# w43TrafficLight_schematic.net
KiCad netlist of a schematic drawn in Altium Designer
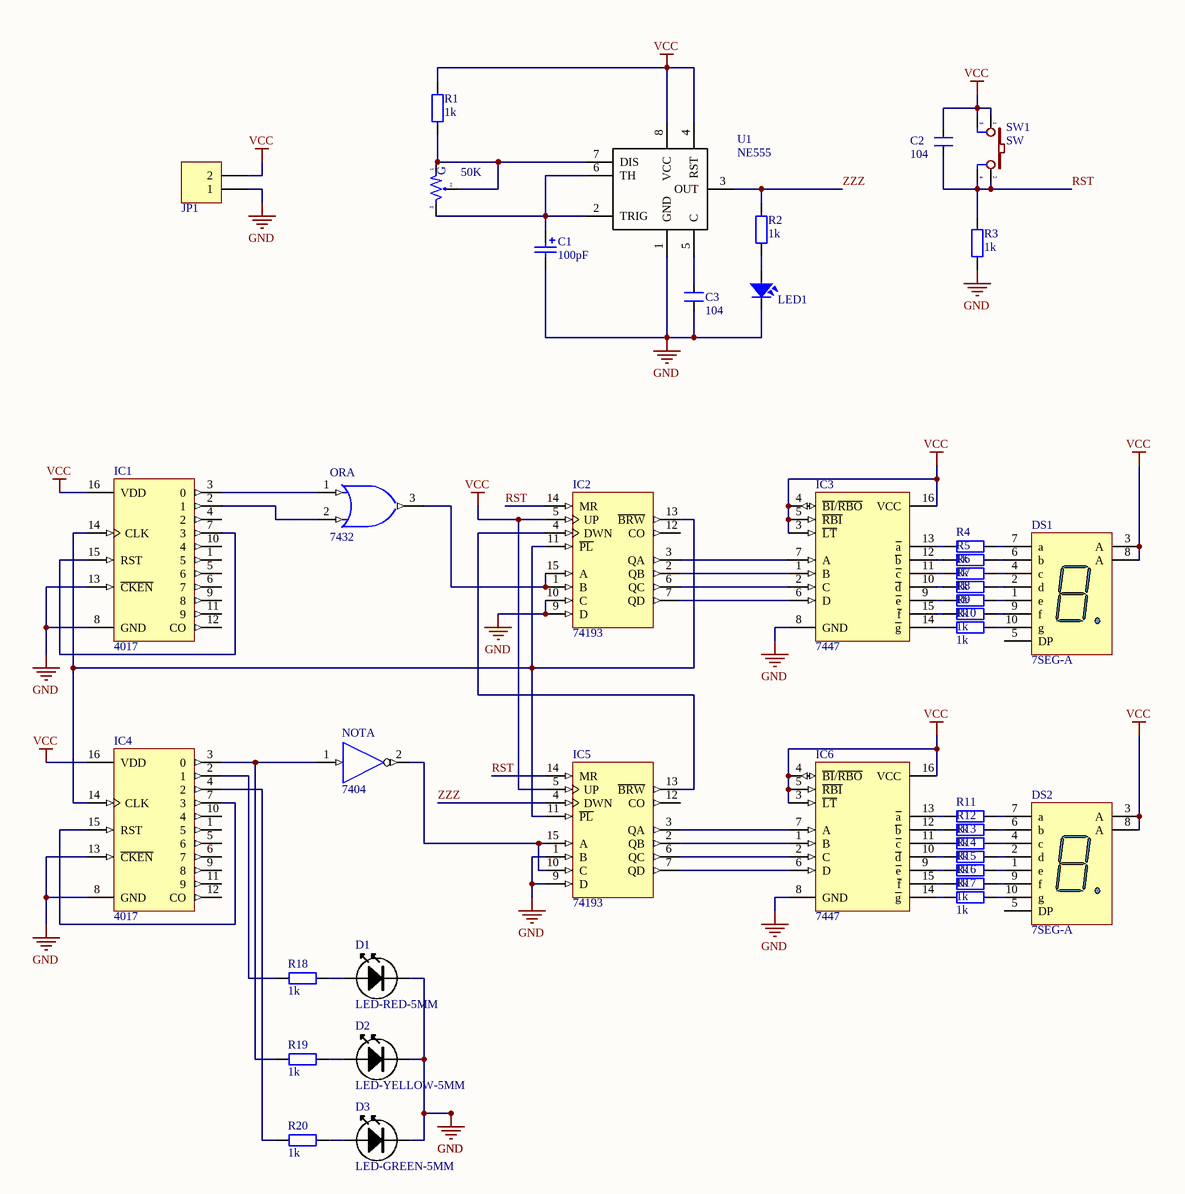
[diagram p0: w43TrafficLight_schematic.SchDoc]

(export (version "E")
  (design (tool "Eeschema 10.0.6"))
  (components
    (comp (ref "C1")
      (value "100pF")
      (footprint "CP1/2")
      (description "Polarized Capacitor (Radial)")
      (fields (field (name "Comment") "Cap Pol"))
      (libsource (lib "PIF_Library") (part "Cap Pol"))
    )
    (comp (ref "C2")
      (value "104")
      (footprint "CN150")
      (description "Capacitor Ceramic")
      (libsource (lib "SRC") (part "CN1.5"))
    )
    (comp (ref "C3")
      (value "104")
      (footprint "CN150")
      (description "Capacitor Ceramic")
      (libsource (lib "SRC") (part "CN1.5"))
    )
    (comp (ref "D1")
      (value "LED-RED-5MM")
      (footprint "LED-5MM-RED")
      (libsource (lib "vh_altium_library") (part "LED-RED-5MM"))
    )
    (comp (ref "D2")
      (value "LED-YELLOW-5MM")
      (footprint "LED-5MM-YELLOW")
      (libsource (lib "vh_altium_library") (part "LED-YELLOW-5MM"))
    )
    (comp (ref "D3")
      (value "LED-GREEN-5MM")
      (footprint "LED-5MM-GREEN")
      (libsource (lib "vh_altium_library") (part "LED-GREEN-5MM"))
    )
    (comp (ref "DS1")
      (value "7SEG-A")
      (footprint "LED7SEG")
      (description "14.2 mm General Purpose Blue 7-Segment Display: CA, RH DP, Gray Surface")
      (fields (field (name "PUBLISHER") "Altium Limited"))
      (libsource (lib "NBBLib-14-03-2012") (part "LED7SEG-A"))
    )
    (comp (ref "DS2")
      (value "7SEG-A")
      (footprint "LED7SEG")
      (description "14.2 mm General Purpose Blue 7-Segment Display: CA, RH DP, Gray Surface")
      (fields (field (name "PUBLISHER") "Altium Limited"))
      (libsource (lib "NBBLib-14-03-2012") (part "LED7SEG-A"))
    )
    (comp (ref "IC1")
      (value "4017")
      (footprint "DIP16")
      (description "Decade Counter/Divider with 10 Decoded Outputs")
      (fields (field (name "DESIGNED BY") "VanDungEvn"))
      (libsource (lib "LIBRARY") (part "4017"))
    )
    (comp (ref "IC2")
      (value "74193")
      (footprint "DIP16/W0.3")
      (description "Synchronous 4-Bit Up/Down Counter")
      (fields (field (name "COPYRIGHT BY") "VanDungEvn@Gmail.com"))
      (libsource (lib "takahashi") (part "74193"))
    )
    (comp (ref "IC3")
      (value "7447")
      (footprint "DIP16")
      (description "BCD to 7-Segment Decoder/Driver")
      (libsource (lib "LIBRARY") (part "7447"))
    )
    (comp (ref "IC4")
      (value "4017")
      (footprint "DIP16")
      (description "Decade Counter/Divider with 10 Decoded Outputs")
      (fields (field (name "DESIGNED BY") "VanDungEvn"))
      (libsource (lib "LIBRARY") (part "4017"))
    )
    (comp (ref "IC5")
      (value "74193")
      (footprint "DIP16/W0.3")
      (description "Synchronous 4-Bit Up/Down Counter")
      (fields (field (name "COPYRIGHT BY") "VanDungEvn@Gmail.com"))
      (libsource (lib "takahashi") (part "74193"))
    )
    (comp (ref "IC6")
      (value "7447")
      (footprint "DIP16")
      (description "BCD to 7-Segment Decoder/Driver")
      (libsource (lib "LIBRARY") (part "7447"))
    )
    (comp (ref "JP1")
      (value "Header 2_1")
      (footprint "HED2")
      (description "Header, 2-Pin")
      (fields (field (name "MANUFACTURER") "Generic Components"))
      (libsource (lib "takahashi") (part "Header 2_1"))
    )
    (comp (ref "LED1")
      (value "LED")
      (footprint "LED-3MM-WHITE")
      (description "LED Single colour Green and Red")
      (libsource (lib "LIBRARY") (part "LED"))
    )
    (comp (ref "NOT")
      (value "7404")
      (footprint "DIP14/W0.3")
      (description "Hex Inverter")
      (libsource (lib "takahashi") (part "7404"))
    )
    (comp (ref "OR")
      (value "7432")
      (footprint "DIP14/W0.3")
      (description "Quad 2-Input OR Gate")
      (libsource (lib "takahashi") (part "7432"))
    )
    (comp (ref "R1")
      (value "1k")
      (footprint "R1/4W")
      (description "Resistor 1/4W")
      (libsource (lib "syhaunguyen") (part "R1/4W"))
    )
    (comp (ref "R2")
      (value "1k")
      (footprint "R1/4W")
      (description "Resistor 1/4W")
      (libsource (lib "syhaunguyen") (part "R1/4W"))
    )
    (comp (ref "R3")
      (value "1k")
      (footprint "R1/4W")
      (description "Resistor 1/4W")
      (libsource (lib "syhaunguyen") (part "R1/4W"))
    )
    (comp (ref "R4")
      (value "1k")
      (footprint "R1/4W")
      (description "Resistor 1/4W")
      (libsource (lib "syhaunguyen") (part "R1/4W"))
    )
    (comp (ref "R5")
      (value "1k")
      (footprint "R1/4W")
      (description "Resistor 1/4W")
      (libsource (lib "syhaunguyen") (part "R1/4W"))
    )
    (comp (ref "R6")
      (value "1k")
      (footprint "R1/4W")
      (description "Resistor 1/4W")
      (libsource (lib "syhaunguyen") (part "R1/4W"))
    )
    (comp (ref "R7")
      (value "1k")
      (footprint "R1/4W")
      (description "Resistor 1/4W")
      (libsource (lib "syhaunguyen") (part "R1/4W"))
    )
    (comp (ref "R8")
      (value "1k")
      (footprint "R1/4W")
      (description "Resistor 1/4W")
      (libsource (lib "syhaunguyen") (part "R1/4W"))
    )
    (comp (ref "R9")
      (value "1k")
      (footprint "R1/4W")
      (description "Resistor 1/4W")
      (libsource (lib "syhaunguyen") (part "R1/4W"))
    )
    (comp (ref "R10")
      (value "1k")
      (footprint "R1/4W")
      (description "Resistor 1/4W")
      (libsource (lib "syhaunguyen") (part "R1/4W"))
    )
    (comp (ref "R11")
      (value "1k")
      (footprint "R1/4W")
      (description "Resistor 1/4W")
      (libsource (lib "syhaunguyen") (part "R1/4W"))
    )
    (comp (ref "R12")
      (value "1k")
      (footprint "R1/4W")
      (description "Resistor 1/4W")
      (libsource (lib "syhaunguyen") (part "R1/4W"))
    )
    (comp (ref "R13")
      (value "1k")
      (footprint "R1/4W")
      (description "Resistor 1/4W")
      (libsource (lib "syhaunguyen") (part "R1/4W"))
    )
    (comp (ref "R14")
      (value "1k")
      (footprint "R1/4W")
      (description "Resistor 1/4W")
      (libsource (lib "syhaunguyen") (part "R1/4W"))
    )
    (comp (ref "R15")
      (value "1k")
      (footprint "R1/4W")
      (description "Resistor 1/4W")
      (libsource (lib "syhaunguyen") (part "R1/4W"))
    )
    (comp (ref "R16")
      (value "1k")
      (footprint "R1/4W")
      (description "Resistor 1/4W")
      (libsource (lib "syhaunguyen") (part "R1/4W"))
    )
    (comp (ref "R17")
      (value "1k")
      (footprint "R1/4W")
      (description "Resistor 1/4W")
      (libsource (lib "syhaunguyen") (part "R1/4W"))
    )
    (comp (ref "R18")
      (value "1k")
      (footprint "R1/4W")
      (description "Resistor 1/4W")
      (libsource (lib "syhaunguyen") (part "R1/4W"))
    )
    (comp (ref "R19")
      (value "1k")
      (footprint "R1/4W")
      (description "Resistor 1/4W")
      (libsource (lib "syhaunguyen") (part "R1/4W"))
    )
    (comp (ref "R20")
      (value "1k")
      (footprint "R1/4W")
      (description "Resistor 1/4W")
      (libsource (lib "syhaunguyen") (part "R1/4W"))
    )
    (comp (ref "SW1")
      (value "SW")
      (footprint "SW4")
      (description "Switch button 4 pin")
      (libsource (lib "takahashi") (part "SW4-1"))
    )
    (comp (ref "U1")
      (value "NE555")
      (footprint "DIP8")
      (description "TIMER IC")
      (fields
        (field (name "MANUFACTURER PART NUMBER") "NE555DT")
        (field (name "MANUFACTURER") "STMicroelectronics")
      )
      (libsource (lib "LIBRARY") (part "NE555"))
    )
    (comp (ref "VR1")
      (value "50K")
      (footprint "VR-S1")
      (description "Var Resistor")
      (libsource (lib "LIBRARY") (part "VR-S"))
    )
  )
  (nets
    (net (code "1") (name "/RST") (class "Default")
      (node (ref "C2") (pin "1") (pinfunction "1_1") (pintype "passive"))
      (node (ref "IC2") (pin "14") (pinfunction "MR_14") (pintype "input"))
      (node (ref "IC5") (pin "14") (pinfunction "MR_14") (pintype "input"))
      (node (ref "R3") (pin "2") (pinfunction "2_2") (pintype "passive"))
      (node (ref "SW1") (pin "2") (pinfunction "2_2") (pintype "passive"))
      (node (ref "SW1") (pin "4") (pinfunction "4_4") (pintype "passive"))
    )
    (net (code "2") (name "/ZZZ") (class "Default")
      (node (ref "IC5") (pin "4") (pinfunction "DWN_4") (pintype "input"))
      (node (ref "R2") (pin "2") (pinfunction "2_2") (pintype "passive"))
      (node (ref "U1") (pin "3") (pinfunction "OUT_3") (pintype "passive"))
    )
    (net (code "3") (name "GND") (class "Default")
      (node (ref "C1") (pin "2") (pinfunction "2_2") (pintype "passive"))
      (node (ref "C3") (pin "1") (pinfunction "1_1") (pintype "passive"))
      (node (ref "D1") (pin "K") (pintype "passive"))
      (node (ref "D2") (pin "K") (pintype "passive"))
      (node (ref "D3") (pin "K") (pintype "passive"))
      (node (ref "IC1") (pin "13") (pinfunction "~{CKEN}_13") (pintype "input"))
      (node (ref "IC1") (pin "8") (pinfunction "GND_8") (pintype "power_in"))
      (node (ref "IC2") (pin "10") (pinfunction "C_10") (pintype "input"))
      (node (ref "IC2") (pin "8") (pinfunction "GND_8") (pintype "power_in"))
      (node (ref "IC2") (pin "9") (pinfunction "D_9") (pintype "input"))
      (node (ref "IC3") (pin "8") (pinfunction "GND_8") (pintype "power_in"))
      (node (ref "IC4") (pin "13") (pinfunction "~{CKEN}_13") (pintype "input"))
      (node (ref "IC4") (pin "8") (pinfunction "GND_8") (pintype "power_in"))
      (node (ref "IC5") (pin "1") (pinfunction "B_1") (pintype "input"))
      (node (ref "IC5") (pin "8") (pinfunction "GND_8") (pintype "power_in"))
      (node (ref "IC5") (pin "9") (pinfunction "D_9") (pintype "input"))
      (node (ref "IC6") (pin "8") (pinfunction "GND_8") (pintype "power_in"))
      (node (ref "JP1") (pin "1") (pinfunction "1_1") (pintype "passive"))
      (node (ref "LED1") (pin "2") (pinfunction "2_2") (pintype "passive"))
      (node (ref "NOT") (pin "7") (pinfunction "GND_7") (pintype "power_in"))
      (node (ref "OR") (pin "7") (pinfunction "GND_7") (pintype "power_in"))
      (node (ref "R3") (pin "1") (pinfunction "1_1") (pintype "passive"))
      (node (ref "U1") (pin "1") (pinfunction "GND_1") (pintype "passive"))
    )
    (net (code "4") (name "Net-(D1-PadA)") (class "Default")
      (node (ref "D1") (pin "A") (pintype "passive"))
      (node (ref "R18") (pin "2") (pinfunction "2_2") (pintype "passive"))
    )
    (net (code "5") (name "Net-(D2-PadA)") (class "Default")
      (node (ref "D2") (pin "A") (pintype "passive"))
      (node (ref "R19") (pin "2") (pinfunction "2_2") (pintype "passive"))
    )
    (net (code "6") (name "Net-(D3-PadA)") (class "Default")
      (node (ref "D3") (pin "A") (pintype "passive"))
      (node (ref "R20") (pin "2") (pinfunction "2_2") (pintype "passive"))
    )
    (net (code "7") (name "Net-(DS1-a)") (class "Default")
      (node (ref "DS1") (pin "7") (pinfunction "a_7") (pintype "passive"))
      (node (ref "R4") (pin "2") (pinfunction "2_2") (pintype "passive"))
    )
    (net (code "8") (name "Net-(DS1-b)") (class "Default")
      (node (ref "DS1") (pin "6") (pinfunction "b_6") (pintype "passive"))
      (node (ref "R5") (pin "2") (pinfunction "2_2") (pintype "passive"))
    )
    (net (code "9") (name "Net-(DS1-c)") (class "Default")
      (node (ref "DS1") (pin "4") (pinfunction "c_4") (pintype "passive"))
      (node (ref "R6") (pin "2") (pinfunction "2_2") (pintype "passive"))
    )
    (net (code "10") (name "Net-(DS1-d)") (class "Default")
      (node (ref "DS1") (pin "2") (pinfunction "d_2") (pintype "passive"))
      (node (ref "R7") (pin "2") (pinfunction "2_2") (pintype "passive"))
    )
    (net (code "11") (name "Net-(DS1-e)") (class "Default")
      (node (ref "DS1") (pin "1") (pinfunction "e_1") (pintype "passive"))
      (node (ref "R8") (pin "2") (pinfunction "2_2") (pintype "passive"))
    )
    (net (code "12") (name "Net-(DS1-f)") (class "Default")
      (node (ref "DS1") (pin "9") (pinfunction "f_9") (pintype "passive"))
      (node (ref "R9") (pin "2") (pinfunction "2_2") (pintype "passive"))
    )
    (net (code "13") (name "Net-(DS1-g)") (class "Default")
      (node (ref "DS1") (pin "10") (pinfunction "g_10") (pintype "passive"))
      (node (ref "R10") (pin "2") (pinfunction "2_2") (pintype "passive"))
    )
    (net (code "14") (name "Net-(DS2-a)") (class "Default")
      (node (ref "DS2") (pin "7") (pinfunction "a_7") (pintype "passive"))
      (node (ref "R11") (pin "2") (pinfunction "2_2") (pintype "passive"))
    )
    (net (code "15") (name "Net-(DS2-b)") (class "Default")
      (node (ref "DS2") (pin "6") (pinfunction "b_6") (pintype "passive"))
      (node (ref "R12") (pin "2") (pinfunction "2_2") (pintype "passive"))
    )
    (net (code "16") (name "Net-(DS2-c)") (class "Default")
      (node (ref "DS2") (pin "4") (pinfunction "c_4") (pintype "passive"))
      (node (ref "R13") (pin "2") (pinfunction "2_2") (pintype "passive"))
    )
    (net (code "17") (name "Net-(DS2-d)") (class "Default")
      (node (ref "DS2") (pin "2") (pinfunction "d_2") (pintype "passive"))
      (node (ref "R14") (pin "2") (pinfunction "2_2") (pintype "passive"))
    )
    (net (code "18") (name "Net-(DS2-e)") (class "Default")
      (node (ref "DS2") (pin "1") (pinfunction "e_1") (pintype "passive"))
      (node (ref "R15") (pin "2") (pinfunction "2_2") (pintype "passive"))
    )
    (net (code "19") (name "Net-(DS2-f)") (class "Default")
      (node (ref "DS2") (pin "9") (pinfunction "f_9") (pintype "passive"))
      (node (ref "R16") (pin "2") (pinfunction "2_2") (pintype "passive"))
    )
    (net (code "20") (name "Net-(DS2-g)") (class "Default")
      (node (ref "DS2") (pin "10") (pinfunction "g_10") (pintype "passive"))
      (node (ref "R17") (pin "2") (pinfunction "2_2") (pintype "passive"))
    )
    (net (code "21") (name "Net-(IC1-0)") (class "Default")
      (node (ref "IC1") (pin "3") (pinfunction "0_3") (pintype "output"))
      (node (ref "OR") (pin "1") (pinfunction "A_1") (pintype "input"))
    )
    (net (code "22") (name "Net-(IC1-1)") (class "Default")
      (node (ref "IC1") (pin "2") (pinfunction "1_2") (pintype "output"))
      (node (ref "OR") (pin "2") (pinfunction "B_2") (pintype "input"))
    )
    (net (code "23") (name "Net-(IC1-3)") (class "Default")
      (node (ref "IC1") (pin "15") (pinfunction "RST_15") (pintype "input"))
      (node (ref "IC1") (pin "7") (pinfunction "3_7") (pintype "output"))
    )
    (net (code "24") (name "Net-(IC1-CLK)") (class "Default")
      (node (ref "IC1") (pin "14") (pinfunction "CLK_14") (pintype "input"))
      (node (ref "IC2") (pin "11") (pinfunction "~{PL}_11") (pintype "input"))
      (node (ref "IC2") (pin "13") (pinfunction "~{BRW}_13") (pintype "output"))
      (node (ref "IC4") (pin "14") (pinfunction "CLK_14") (pintype "input"))
      (node (ref "IC5") (pin "11") (pinfunction "~{PL}_11") (pintype "input"))
    )
    (net (code "25") (name "Net-(IC2-A)") (class "Default")
      (node (ref "IC2") (pin "1") (pinfunction "B_1") (pintype "input"))
      (node (ref "IC2") (pin "15") (pinfunction "A_15") (pintype "input"))
      (node (ref "OR") (pin "3") (pinfunction "Y_3") (pintype "output"))
    )
    (net (code "26") (name "Net-(IC2-DWN)") (class "Default")
      (node (ref "IC2") (pin "4") (pinfunction "DWN_4") (pintype "input"))
      (node (ref "IC5") (pin "13") (pinfunction "~{BRW}_13") (pintype "output"))
    )
    (net (code "27") (name "Net-(IC2-QA)") (class "Default")
      (node (ref "IC2") (pin "3") (pinfunction "QA_3") (pintype "output"))
      (node (ref "IC3") (pin "7") (pinfunction "A_7") (pintype "input"))
    )
    (net (code "28") (name "Net-(IC2-QB)") (class "Default")
      (node (ref "IC2") (pin "2") (pinfunction "QB_2") (pintype "output"))
      (node (ref "IC3") (pin "1") (pinfunction "B_1") (pintype "input"))
    )
    (net (code "29") (name "Net-(IC2-QC)") (class "Default")
      (node (ref "IC2") (pin "6") (pinfunction "QC_6") (pintype "output"))
      (node (ref "IC3") (pin "2") (pinfunction "C_2") (pintype "input"))
    )
    (net (code "30") (name "Net-(IC2-QD)") (class "Default")
      (node (ref "IC2") (pin "7") (pinfunction "QD_7") (pintype "output"))
      (node (ref "IC3") (pin "6") (pinfunction "D_6") (pintype "input"))
    )
    (net (code "31") (name "Net-(IC3-~{a})") (class "Default")
      (node (ref "IC3") (pin "13") (pinfunction "~{a}_13") (pintype "open_collector"))
      (node (ref "R4") (pin "1") (pinfunction "1_1") (pintype "passive"))
    )
    (net (code "32") (name "Net-(IC3-~{b})") (class "Default")
      (node (ref "IC3") (pin "12") (pinfunction "~{b}_12") (pintype "open_collector"))
      (node (ref "R5") (pin "1") (pinfunction "1_1") (pintype "passive"))
    )
    (net (code "33") (name "Net-(IC3-~{c})") (class "Default")
      (node (ref "IC3") (pin "11") (pinfunction "~{c}_11") (pintype "open_collector"))
      (node (ref "R6") (pin "1") (pinfunction "1_1") (pintype "passive"))
    )
    (net (code "34") (name "Net-(IC3-~{d})") (class "Default")
      (node (ref "IC3") (pin "10") (pinfunction "~{d}_10") (pintype "open_collector"))
      (node (ref "R7") (pin "1") (pinfunction "1_1") (pintype "passive"))
    )
    (net (code "35") (name "Net-(IC3-~{e})") (class "Default")
      (node (ref "IC3") (pin "9") (pinfunction "~{e}_9") (pintype "open_collector"))
      (node (ref "R8") (pin "1") (pinfunction "1_1") (pintype "passive"))
    )
    (net (code "36") (name "Net-(IC3-~{f})") (class "Default")
      (node (ref "IC3") (pin "15") (pinfunction "~{f}_15") (pintype "open_collector"))
      (node (ref "R9") (pin "1") (pinfunction "1_1") (pintype "passive"))
    )
    (net (code "37") (name "Net-(IC3-~{g})") (class "Default")
      (node (ref "IC3") (pin "14") (pinfunction "~{g}_14") (pintype "open_collector"))
      (node (ref "R10") (pin "1") (pinfunction "1_1") (pintype "passive"))
    )
    (net (code "38") (name "Net-(IC4-0)") (class "Default")
      (node (ref "IC4") (pin "3") (pinfunction "0_3") (pintype "output"))
      (node (ref "NOT") (pin "1") (pinfunction "A_1") (pintype "input"))
      (node (ref "R19") (pin "1") (pinfunction "1_1") (pintype "passive"))
    )
    (net (code "39") (name "Net-(IC4-1)") (class "Default")
      (node (ref "IC4") (pin "2") (pinfunction "1_2") (pintype "output"))
      (node (ref "R18") (pin "1") (pinfunction "1_1") (pintype "passive"))
    )
    (net (code "40") (name "Net-(IC4-2)") (class "Default")
      (node (ref "IC4") (pin "4") (pinfunction "2_4") (pintype "output"))
      (node (ref "R20") (pin "1") (pinfunction "1_1") (pintype "passive"))
    )
    (net (code "41") (name "Net-(IC4-3)") (class "Default")
      (node (ref "IC4") (pin "15") (pinfunction "RST_15") (pintype "input"))
      (node (ref "IC4") (pin "7") (pinfunction "3_7") (pintype "output"))
    )
    (net (code "42") (name "Net-(IC5-A)") (class "Default")
      (node (ref "IC5") (pin "10") (pinfunction "C_10") (pintype "input"))
      (node (ref "IC5") (pin "15") (pinfunction "A_15") (pintype "input"))
      (node (ref "NOT") (pin "2") (pinfunction "~{O}_2") (pintype "output"))
    )
    (net (code "43") (name "Net-(IC5-QA)") (class "Default")
      (node (ref "IC5") (pin "3") (pinfunction "QA_3") (pintype "output"))
      (node (ref "IC6") (pin "7") (pinfunction "A_7") (pintype "input"))
    )
    (net (code "44") (name "Net-(IC5-QB)") (class "Default")
      (node (ref "IC5") (pin "2") (pinfunction "QB_2") (pintype "output"))
      (node (ref "IC6") (pin "1") (pinfunction "B_1") (pintype "input"))
    )
    (net (code "45") (name "Net-(IC5-QC)") (class "Default")
      (node (ref "IC5") (pin "6") (pinfunction "QC_6") (pintype "output"))
      (node (ref "IC6") (pin "2") (pinfunction "C_2") (pintype "input"))
    )
    (net (code "46") (name "Net-(IC5-QD)") (class "Default")
      (node (ref "IC5") (pin "7") (pinfunction "QD_7") (pintype "output"))
      (node (ref "IC6") (pin "6") (pinfunction "D_6") (pintype "input"))
    )
    (net (code "47") (name "Net-(IC6-~{a})") (class "Default")
      (node (ref "IC6") (pin "13") (pinfunction "~{a}_13") (pintype "open_collector"))
      (node (ref "R11") (pin "1") (pinfunction "1_1") (pintype "passive"))
    )
    (net (code "48") (name "Net-(IC6-~{b})") (class "Default")
      (node (ref "IC6") (pin "12") (pinfunction "~{b}_12") (pintype "open_collector"))
      (node (ref "R12") (pin "1") (pinfunction "1_1") (pintype "passive"))
    )
    (net (code "49") (name "Net-(IC6-~{c})") (class "Default")
      (node (ref "IC6") (pin "11") (pinfunction "~{c}_11") (pintype "open_collector"))
      (node (ref "R13") (pin "1") (pinfunction "1_1") (pintype "passive"))
    )
    (net (code "50") (name "Net-(IC6-~{d})") (class "Default")
      (node (ref "IC6") (pin "10") (pinfunction "~{d}_10") (pintype "open_collector"))
      (node (ref "R14") (pin "1") (pinfunction "1_1") (pintype "passive"))
    )
    (net (code "51") (name "Net-(IC6-~{e})") (class "Default")
      (node (ref "IC6") (pin "9") (pinfunction "~{e}_9") (pintype "open_collector"))
      (node (ref "R15") (pin "1") (pinfunction "1_1") (pintype "passive"))
    )
    (net (code "52") (name "Net-(IC6-~{f})") (class "Default")
      (node (ref "IC6") (pin "15") (pinfunction "~{f}_15") (pintype "open_collector"))
      (node (ref "R16") (pin "1") (pinfunction "1_1") (pintype "passive"))
    )
    (net (code "53") (name "Net-(IC6-~{g})") (class "Default")
      (node (ref "IC6") (pin "14") (pinfunction "~{g}_14") (pintype "open_collector"))
      (node (ref "R17") (pin "1") (pinfunction "1_1") (pintype "passive"))
    )
    (net (code "54") (name "Net-(LED1-Pad1)") (class "Default")
      (node (ref "LED1") (pin "1") (pinfunction "1_1") (pintype "passive"))
      (node (ref "R2") (pin "1") (pinfunction "1_1") (pintype "passive"))
    )
    (net (code "55") (name "Net-(U1-C)") (class "Default")
      (node (ref "C3") (pin "2") (pinfunction "2_2") (pintype "passive"))
      (node (ref "U1") (pin "5") (pinfunction "C_5") (pintype "passive"))
    )
    (net (code "56") (name "Net-(U1-DIS)") (class "Default")
      (node (ref "R1") (pin "1") (pinfunction "1_1") (pintype "passive"))
      (node (ref "U1") (pin "7") (pinfunction "DIS_7") (pintype "passive"))
      (node (ref "VR1") (pin "1") (pinfunction "1_1") (pintype "passive"))
      (node (ref "VR1") (pin "2") (pinfunction "2_2") (pintype "passive"))
    )
    (net (code "57") (name "Net-(U1-TH)") (class "Default")
      (node (ref "C1") (pin "1") (pinfunction "1_1") (pintype "passive"))
      (node (ref "U1") (pin "2") (pinfunction "TRIG_2") (pintype "passive"))
      (node (ref "U1") (pin "6") (pinfunction "TH_6") (pintype "passive"))
      (node (ref "VR1") (pin "3") (pinfunction "3_3") (pintype "passive"))
    )
    (net (code "58") (name "VCC") (class "Default")
      (node (ref "C2") (pin "2") (pinfunction "2_2") (pintype "passive"))
      (node (ref "DS1") (pin "3") (pinfunction "A_3") (pintype "passive"))
      (node (ref "DS1") (pin "8") (pinfunction "A_8") (pintype "passive"))
      (node (ref "DS2") (pin "3") (pinfunction "A_3") (pintype "passive"))
      (node (ref "DS2") (pin "8") (pinfunction "A_8") (pintype "passive"))
      (node (ref "IC1") (pin "16") (pinfunction "VDD_16") (pintype "power_in"))
      (node (ref "IC2") (pin "16") (pinfunction "VCC_16") (pintype "power_in"))
      (node (ref "IC2") (pin "5") (pinfunction "UP_5") (pintype "input"))
      (node (ref "IC3") (pin "16") (pinfunction "VCC_16") (pintype "power_in"))
      (node (ref "IC3") (pin "3") (pinfunction "~{LT}_3") (pintype "input"))
      (node (ref "IC3") (pin "4") (pinfunction "~{BI}/~{RBO}_4") (pintype "bidirectional"))
      (node (ref "IC3") (pin "5") (pinfunction "~{RBI}_5") (pintype "input"))
      (node (ref "IC4") (pin "16") (pinfunction "VDD_16") (pintype "power_in"))
      (node (ref "IC5") (pin "16") (pinfunction "VCC_16") (pintype "power_in"))
      (node (ref "IC5") (pin "5") (pinfunction "UP_5") (pintype "input"))
      (node (ref "IC6") (pin "16") (pinfunction "VCC_16") (pintype "power_in"))
      (node (ref "IC6") (pin "3") (pinfunction "~{LT}_3") (pintype "input"))
      (node (ref "IC6") (pin "4") (pinfunction "~{BI}/~{RBO}_4") (pintype "bidirectional"))
      (node (ref "IC6") (pin "5") (pinfunction "~{RBI}_5") (pintype "input"))
      (node (ref "JP1") (pin "2") (pinfunction "2_2") (pintype "passive"))
      (node (ref "NOT") (pin "14") (pinfunction "VCC_14") (pintype "power_in"))
      (node (ref "OR") (pin "14") (pinfunction "VCC_14") (pintype "power_in"))
      (node (ref "R1") (pin "2") (pinfunction "2_2") (pintype "passive"))
      (node (ref "SW1") (pin "1") (pinfunction "1_1") (pintype "passive"))
      (node (ref "SW1") (pin "3") (pinfunction "3_3") (pintype "passive"))
      (node (ref "U1") (pin "4") (pinfunction "RST_4") (pintype "passive"))
      (node (ref "U1") (pin "8") (pinfunction "VCC_8") (pintype "passive"))
    )
    (net (code "59") (name "unconnected-(DS1-DP-Pad5)") (class "Default")
      (node (ref "DS1") (pin "5") (pinfunction "DP_5") (pintype "passive"))
    )
    (net (code "60") (name "unconnected-(DS2-DP-Pad5)") (class "Default")
      (node (ref "DS2") (pin "5") (pinfunction "DP_5") (pintype "passive"))
    )
    (net (code "61") (name "unconnected-(IC1-2-Pad4)") (class "Default")
      (node (ref "IC1") (pin "4") (pinfunction "2_4") (pintype "output"))
    )
    (net (code "62") (name "unconnected-(IC1-4-Pad10)") (class "Default")
      (node (ref "IC1") (pin "10") (pinfunction "4_10") (pintype "output"))
    )
    (net (code "63") (name "unconnected-(IC1-5-Pad1)") (class "Default")
      (node (ref "IC1") (pin "1") (pinfunction "5_1") (pintype "output"))
    )
    (net (code "64") (name "unconnected-(IC1-6-Pad5)") (class "Default")
      (node (ref "IC1") (pin "5") (pinfunction "6_5") (pintype "output"))
    )
    (net (code "65") (name "unconnected-(IC1-7-Pad6)") (class "Default")
      (node (ref "IC1") (pin "6") (pinfunction "7_6") (pintype "output"))
    )
    (net (code "66") (name "unconnected-(IC1-8-Pad9)") (class "Default")
      (node (ref "IC1") (pin "9") (pinfunction "8_9") (pintype "output"))
    )
    (net (code "67") (name "unconnected-(IC1-9-Pad11)") (class "Default")
      (node (ref "IC1") (pin "11") (pinfunction "9_11") (pintype "output"))
    )
    (net (code "68") (name "unconnected-(IC1-CO-Pad12)") (class "Default")
      (node (ref "IC1") (pin "12") (pinfunction "CO_12") (pintype "output"))
    )
    (net (code "69") (name "unconnected-(IC2-CO-Pad12)") (class "Default")
      (node (ref "IC2") (pin "12") (pinfunction "CO_12") (pintype "output"))
    )
    (net (code "70") (name "unconnected-(IC4-4-Pad10)") (class "Default")
      (node (ref "IC4") (pin "10") (pinfunction "4_10") (pintype "output"))
    )
    (net (code "71") (name "unconnected-(IC4-5-Pad1)") (class "Default")
      (node (ref "IC4") (pin "1") (pinfunction "5_1") (pintype "output"))
    )
    (net (code "72") (name "unconnected-(IC4-6-Pad5)") (class "Default")
      (node (ref "IC4") (pin "5") (pinfunction "6_5") (pintype "output"))
    )
    (net (code "73") (name "unconnected-(IC4-7-Pad6)") (class "Default")
      (node (ref "IC4") (pin "6") (pinfunction "7_6") (pintype "output"))
    )
    (net (code "74") (name "unconnected-(IC4-8-Pad9)") (class "Default")
      (node (ref "IC4") (pin "9") (pinfunction "8_9") (pintype "output"))
    )
    (net (code "75") (name "unconnected-(IC4-9-Pad11)") (class "Default")
      (node (ref "IC4") (pin "11") (pinfunction "9_11") (pintype "output"))
    )
    (net (code "76") (name "unconnected-(IC4-CO-Pad12)") (class "Default")
      (node (ref "IC4") (pin "12") (pinfunction "CO_12") (pintype "output"))
    )
    (net (code "77") (name "unconnected-(IC5-CO-Pad12)") (class "Default")
      (node (ref "IC5") (pin "12") (pinfunction "CO_12") (pintype "output"))
    )
  )
)
